# aq6.net
KiCad netlist of a schematic drawn in EAGLE
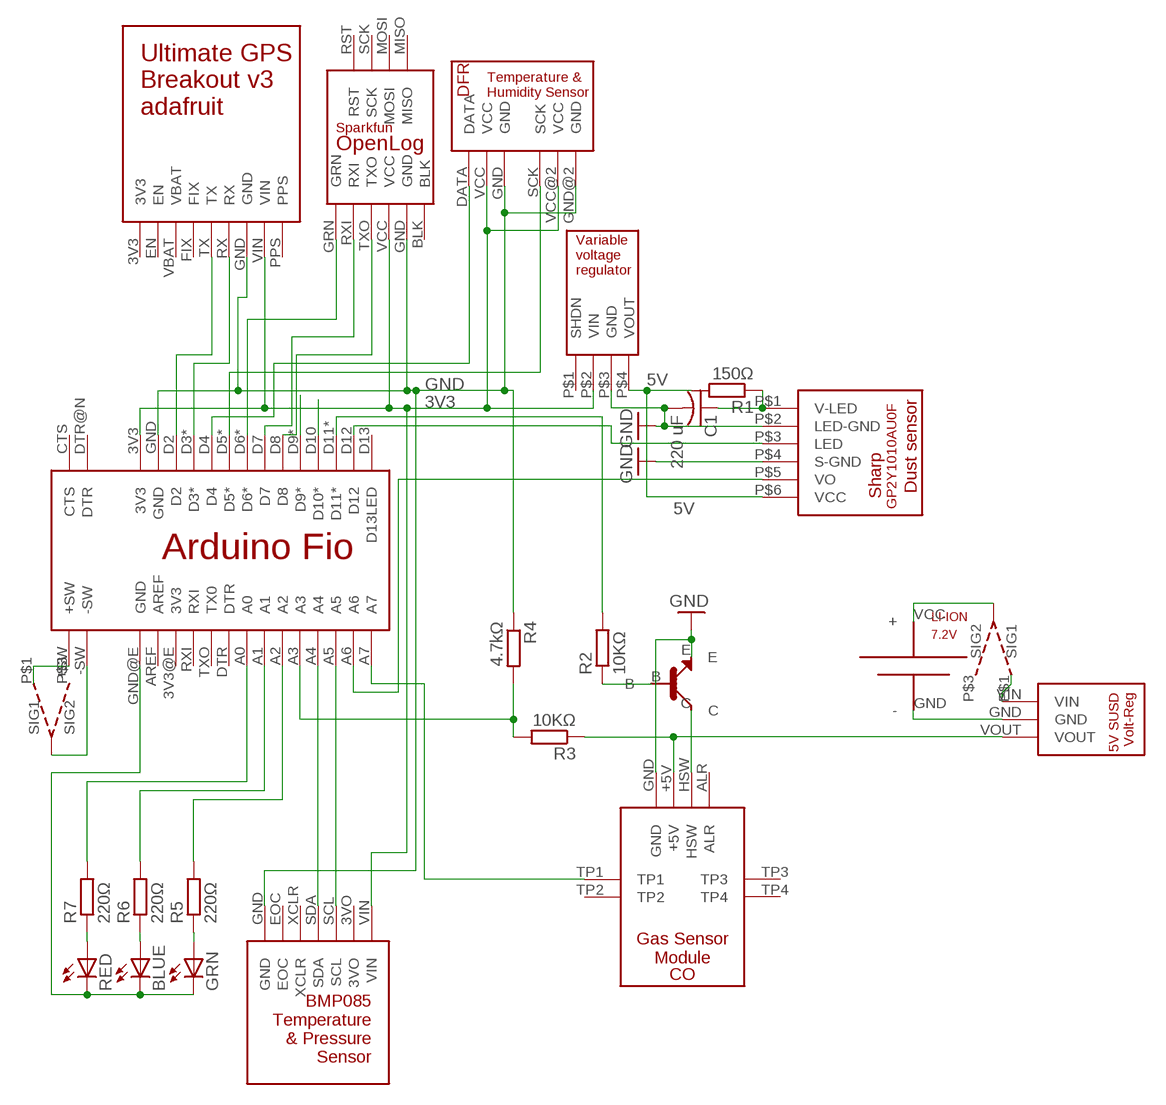
[diagram p0: schematic, sheet 1]

(export (version "E")
  (design (tool "Eeschema 10.0.6"))
  (components
    (comp (ref "BLUE")
      (value "LED5MM")
      (footprint "eagle-import:LED5MM")
      (libsource (lib "eagle-import") (part "LED5MM"))
    )
    (comp (ref "C1")
      (value "220 uF")
      (footprint "eagle-import:C050-025X075")
      (libsource (lib "eagle-import") (part "C-US050-025X075"))
    )
    (comp (ref "CO")
      (value "CO")
      (footprint "eagle-import:GSM_PARALLAX")
      (libsource (lib "eagle-import") (part "CO"))
    )
    (comp (ref "GRN")
      (value "LED5MM")
      (footprint "eagle-import:LED5MM")
      (libsource (lib "eagle-import") (part "LED5MM"))
    )
    (comp (ref "LI-ION")
      (value "7.2V")
      (footprint "eagle-import:BATTERY_WITH_WIRE_HOLES")
      (libsource (lib "eagle-import") (part "BATTERY_WITH_PCB_HOLES"))
    )
    (comp (ref "R1")
      (value "150Ω")
      (footprint "eagle-import:0207_15")
      (libsource (lib "eagle-import") (part "R-EU_0207/15"))
    )
    (comp (ref "R2")
      (value "10KΩ")
      (footprint "eagle-import:0204_7")
      (libsource (lib "eagle-import") (part "resistor_R-EU_0204/7"))
    )
    (comp (ref "R3")
      (value "10KΩ")
      (footprint "eagle-import:0204_7")
      (libsource (lib "eagle-import") (part "resistor_R-EU_0204/7"))
    )
    (comp (ref "R4")
      (value "4.7kΩ")
      (footprint "eagle-import:0204_7")
      (libsource (lib "eagle-import") (part "resistor_R-EU_0204/7"))
    )
    (comp (ref "R5")
      (value "220Ω")
      (footprint "eagle-import:0204_7")
      (libsource (lib "eagle-import") (part "resistor_R-EU_0204/7"))
    )
    (comp (ref "R6")
      (value "220Ω")
      (footprint "eagle-import:0204_7")
      (libsource (lib "eagle-import") (part "resistor_R-EU_0204/7"))
    )
    (comp (ref "R7")
      (value "220Ω")
      (footprint "eagle-import:0204_7")
      (libsource (lib "eagle-import") (part "resistor_R-EU_0204/7"))
    )
    (comp (ref "RED")
      (value "LED5MM")
      (footprint "eagle-import:LED5MM")
      (libsource (lib "eagle-import") (part "LED5MM"))
    )
    (comp (ref "U$1")
      (value "SHARP_DUST_SENSOR6PIN")
      (footprint "eagle-import:6PIN")
      (libsource (lib "eagle-import") (part "SHARP_DUST_SENSOR6PIN"))
    )
    (comp (ref "U$2")
      (value "ARDUINO_FIO")
      (footprint "eagle-import:ARDUINO_FIO")
      (libsource (lib "eagle-import") (part "ARDUINO_FIO"))
    )
    (comp (ref "U$3")
      (value "POLOLU_VAR_VOLTAGE_REG")
      (footprint "eagle-import:POLOLU_VAR_VOLTAGE_REG")
      (libsource (lib "eagle-import") (part "POLOLU_VAR_VOLTAGE_REG"))
    )
    (comp (ref "U$4")
      (value "ADAFRUIT_GPS_V3")
      (footprint "eagle-import:ADAFRUIT_GPS_V3")
      (libsource (lib "eagle-import") (part "ADAFRUIT_GPS_V3"))
    )
    (comp (ref "U$5")
      (value "SPARKFUN_OPENLOG")
      (footprint "eagle-import:SPARKFUN_OPENLOG")
      (libsource (lib "eagle-import") (part "SPARKFUN_OPENLOG"))
    )
    (comp (ref "U$6")
      (value "DFR_TEMP_HUMIDITY")
      (footprint "eagle-import:DFR_TEMP_HUMIDITY")
      (libsource (lib "eagle-import") (part "DFR_TEMP_HUMIDITY"))
    )
    (comp (ref "U$7")
      (value "5V_SUSD_VOLT_REG")
      (footprint "eagle-import:5V_SUSD_VOLT_REG")
      (libsource (lib "eagle-import") (part "5V_SUSD_VOLT_REG"))
    )
    (comp (ref "U$8")
      (value "BMP085")
      (footprint "eagle-import:BMP085")
      (libsource (lib "eagle-import") (part "BMP085"))
    )
    (comp (ref "U$10")
      (value "SWITCH")
      (footprint "eagle-import:SWITCH")
      (libsource (lib "eagle-import") (part "SWITCH"))
    )
    (comp (ref "U$11")
      (value "SWITCH")
      (footprint "eagle-import:SWITCH")
      (libsource (lib "eagle-import") (part "SWITCH"))
    )
    (comp (ref "U$12")
      (value "NPN")
      (footprint "eagle-import:NPN")
      (libsource (lib "eagle-import") (part "NPN"))
    )
  )
  (nets
    (net (code "1") (name "/3V3") (class "Default")
      (node (ref "U$2") (pin "3V3") (pinfunction "3V3_3V3") (pintype "bidirectional"))
      (node (ref "U$3") (pin "P$2") (pinfunction "VIN_P$2") (pintype "bidirectional"))
      (node (ref "U$4") (pin "VIN") (pinfunction "VIN_VIN") (pintype "bidirectional"))
      (node (ref "U$5") (pin "VCC") (pinfunction "VCC_VCC") (pintype "bidirectional"))
      (node (ref "U$6") (pin "VCC") (pinfunction "VCC_VCC") (pintype "bidirectional"))
      (node (ref "U$6") (pin "VCC@2") (pinfunction "VCC_VCC@2") (pintype "bidirectional"))
      (node (ref "U$8") (pin "VIN") (pinfunction "VIN_VIN") (pintype "power_in"))
    )
    (net (code "2") (name "/3VO") (class "Default")
      (node (ref "U$8") (pin "3VO") (pinfunction "3VO_3VO") (pintype "power_in"))
    )
    (net (code "3") (name "/5V") (class "Default")
      (node (ref "R1") (pin "2") (pinfunction "2_2") (pintype "passive"))
      (node (ref "U$1") (pin "P$6") (pinfunction "VCC_P$6") (pintype "bidirectional"))
      (node (ref "U$3") (pin "P$4") (pinfunction "VOUT_P$4") (pintype "bidirectional"))
    )
    (net (code "4") (name "GND") (class "Default")
      (node (ref "BLUE") (pin "K") (pinfunction "C_K") (pintype "passive"))
      (node (ref "C1") (pin "2") (pinfunction "2_2") (pintype "passive"))
      (node (ref "CO") (pin "GND") (pinfunction "GND_GND") (pintype "power_in"))
      (node (ref "GRN") (pin "K") (pinfunction "C_K") (pintype "passive"))
      (node (ref "LI-ION") (pin "GND") (pinfunction "-_GND") (pintype "bidirectional"))
      (node (ref "R4") (pin "1") (pinfunction "1_1") (pintype "passive"))
      (node (ref "RED") (pin "K") (pinfunction "C_K") (pintype "passive"))
      (node (ref "U$1") (pin "P$2") (pinfunction "LED-GND_P$2") (pintype "bidirectional"))
      (node (ref "U$1") (pin "P$4") (pinfunction "S-GND_P$4") (pintype "bidirectional"))
      (node (ref "U$12") (pin "E") (pinfunction "E_E") (pintype "bidirectional"))
      (node (ref "U$2") (pin "GND") (pinfunction "GND_GND") (pintype "bidirectional"))
      (node (ref "U$2") (pin "GND@E") (pinfunction "GND_GND@E") (pintype "bidirectional"))
      (node (ref "U$3") (pin "P$3") (pinfunction "GND_P$3") (pintype "bidirectional"))
      (node (ref "U$4") (pin "GND") (pinfunction "GND_GND") (pintype "bidirectional"))
      (node (ref "U$5") (pin "GND") (pinfunction "GND_GND") (pintype "bidirectional"))
      (node (ref "U$6") (pin "GND") (pinfunction "GND_GND") (pintype "bidirectional"))
      (node (ref "U$6") (pin "GND@2") (pinfunction "GND_GND@2") (pintype "bidirectional"))
      (node (ref "U$7") (pin "GND") (pinfunction "GND_GND") (pintype "bidirectional"))
      (node (ref "U$8") (pin "GND") (pinfunction "GND_GND") (pintype "power_in"))
    )
    (net (code "5") (name "Net-(BLUE-PadA)") (class "Default")
      (node (ref "BLUE") (pin "A") (pinfunction "A_A") (pintype "passive"))
      (node (ref "R6") (pin "1") (pinfunction "1_1") (pintype "passive"))
    )
    (net (code "6") (name "Net-(CO-Pad+5V)") (class "Default")
      (node (ref "CO") (pin "+5V") (pinfunction "+5V_+5V") (pintype "power_in"))
      (node (ref "R3") (pin "1") (pinfunction "1_1") (pintype "passive"))
      (node (ref "U$7") (pin "VOUT") (pinfunction "VOUT_VOUT") (pintype "bidirectional"))
    )
    (net (code "7") (name "Net-(CO-PadHSW)") (class "Default")
      (node (ref "CO") (pin "HSW") (pinfunction "HSW_HSW") (pintype "bidirectional"))
      (node (ref "U$12") (pin "C") (pinfunction "C_C") (pintype "bidirectional"))
    )
    (net (code "8") (name "Net-(CO-PadTP1)") (class "Default")
      (node (ref "CO") (pin "TP1") (pinfunction "TP1_TP1") (pintype "output"))
      (node (ref "U$2") (pin "A7") (pinfunction "A7_A7") (pintype "bidirectional"))
    )
    (net (code "9") (name "Net-(GRN-PadA)") (class "Default")
      (node (ref "GRN") (pin "A") (pinfunction "A_A") (pintype "passive"))
      (node (ref "R5") (pin "1") (pinfunction "1_1") (pintype "passive"))
    )
    (net (code "10") (name "Net-(LI-ION-+)") (class "Default")
      (node (ref "LI-ION") (pin "VCC") (pinfunction "+_VCC") (pintype "bidirectional"))
      (node (ref "U$11") (pin "P$2") (pinfunction "SIG_OUT_P$2") (pintype "bidirectional"))
    )
    (net (code "11") (name "Net-(R2-Pad1)") (class "Default")
      (node (ref "R2") (pin "1") (pinfunction "1_1") (pintype "passive"))
      (node (ref "U$12") (pin "B") (pinfunction "B_B") (pintype "bidirectional"))
    )
    (net (code "12") (name "Net-(R2-Pad2)") (class "Default")
      (node (ref "R2") (pin "2") (pinfunction "2_2") (pintype "passive"))
      (node (ref "U$2") (pin "D11*") (pinfunction "D11*_D11*") (pintype "bidirectional"))
    )
    (net (code "13") (name "Net-(R3-Pad2)") (class "Default")
      (node (ref "R3") (pin "2") (pinfunction "2_2") (pintype "passive"))
      (node (ref "R4") (pin "2") (pinfunction "2_2") (pintype "passive"))
      (node (ref "U$2") (pin "A3") (pinfunction "A3_A3") (pintype "bidirectional"))
    )
    (net (code "14") (name "Net-(R5-Pad2)") (class "Default")
      (node (ref "R5") (pin "2") (pinfunction "2_2") (pintype "passive"))
      (node (ref "U$2") (pin "A2") (pinfunction "A2_A2") (pintype "bidirectional"))
    )
    (net (code "15") (name "Net-(R6-Pad2)") (class "Default")
      (node (ref "R6") (pin "2") (pinfunction "2_2") (pintype "passive"))
      (node (ref "U$2") (pin "A1") (pinfunction "A1_A1") (pintype "bidirectional"))
    )
    (net (code "16") (name "Net-(R7-Pad1)") (class "Default")
      (node (ref "R7") (pin "1") (pinfunction "1_1") (pintype "passive"))
      (node (ref "RED") (pin "A") (pinfunction "A_A") (pintype "passive"))
    )
    (net (code "17") (name "Net-(R7-Pad2)") (class "Default")
      (node (ref "R7") (pin "2") (pinfunction "2_2") (pintype "passive"))
      (node (ref "U$2") (pin "A0") (pinfunction "A0_A0") (pintype "bidirectional"))
    )
    (net (code "18") (name "Net-(U$1-LED)") (class "Default")
      (node (ref "U$1") (pin "P$3") (pinfunction "LED_P$3") (pintype "bidirectional"))
      (node (ref "U$2") (pin "D12") (pinfunction "D12_D12") (pintype "bidirectional"))
    )
    (net (code "19") (name "Net-(U$1-V-LED)") (class "Default")
      (node (ref "C1") (pin "1") (pinfunction "1_1") (pintype "passive"))
      (node (ref "R1") (pin "1") (pinfunction "1_1") (pintype "passive"))
      (node (ref "U$1") (pin "P$1") (pinfunction "V-LED_P$1") (pintype "bidirectional"))
    )
    (net (code "20") (name "Net-(U$1-VO)") (class "Default")
      (node (ref "U$1") (pin "P$5") (pinfunction "VO_P$5") (pintype "bidirectional"))
      (node (ref "U$2") (pin "A6") (pinfunction "A6_A6") (pintype "bidirectional"))
    )
    (net (code "21") (name "Net-(U$2-PadA4)") (class "Default")
      (node (ref "U$2") (pin "A4") (pinfunction "A4_A4") (pintype "bidirectional"))
      (node (ref "U$8") (pin "SDA") (pinfunction "SDA_SDA") (pintype "bidirectional"))
    )
    (net (code "22") (name "Net-(U$2-PadA5)") (class "Default")
      (node (ref "U$2") (pin "A5") (pinfunction "A5_A5") (pintype "bidirectional"))
      (node (ref "U$8") (pin "SCL") (pinfunction "SCL_SCL") (pintype "bidirectional"))
    )
    (net (code "23") (name "Net-(U$2-PadD2)") (class "Default")
      (node (ref "U$2") (pin "D2") (pinfunction "D2_D2") (pintype "bidirectional"))
      (node (ref "U$4") (pin "TX") (pinfunction "TX_TX") (pintype "bidirectional"))
    )
    (net (code "24") (name "Net-(U$2-PadD3*)") (class "Default")
      (node (ref "U$2") (pin "D3*") (pinfunction "D3*_D3*") (pintype "bidirectional"))
      (node (ref "U$4") (pin "RX") (pinfunction "RX_RX") (pintype "bidirectional"))
    )
    (net (code "25") (name "Net-(U$2-PadD4)") (class "Default")
      (node (ref "U$2") (pin "D4") (pinfunction "D4_D4") (pintype "bidirectional"))
      (node (ref "U$6") (pin "DATA") (pinfunction "DATA_DATA") (pintype "bidirectional"))
    )
    (net (code "26") (name "Net-(U$2-PadD5*)") (class "Default")
      (node (ref "U$2") (pin "D5*") (pinfunction "D5*_D5*") (pintype "bidirectional"))
      (node (ref "U$6") (pin "SCK") (pinfunction "SCK_SCK") (pintype "bidirectional"))
    )
    (net (code "27") (name "Net-(U$2-PadD6*)") (class "Default")
      (node (ref "U$2") (pin "D6*") (pinfunction "D6*_D6*") (pintype "bidirectional"))
      (node (ref "U$5") (pin "GRN") (pinfunction "GRN_GRN") (pintype "bidirectional"))
    )
    (net (code "28") (name "Net-(U$2-PadD7)") (class "Default")
      (node (ref "U$2") (pin "D7") (pinfunction "D7_D7") (pintype "bidirectional"))
      (node (ref "U$5") (pin "RXI") (pinfunction "RXI_RXI") (pintype "bidirectional"))
    )
    (net (code "29") (name "Net-(U$2-PadD8)") (class "Default")
      (node (ref "U$2") (pin "D8") (pinfunction "D8_D8") (pintype "bidirectional"))
      (node (ref "U$5") (pin "TXO") (pinfunction "TXO_TXO") (pintype "bidirectional"))
    )
    (net (code "30") (name "Net-(U$10-SIG1)") (class "Default")
      (node (ref "U$10") (pin "P$1") (pinfunction "SIG1_P$1") (pintype "bidirectional"))
      (node (ref "U$2") (pin "+SW") (pinfunction "+SW_+SW") (pintype "bidirectional"))
    )
    (net (code "31") (name "Net-(U$10-SIG_OUT)") (class "Default")
      (node (ref "U$10") (pin "P$2") (pinfunction "SIG_OUT_P$2") (pintype "bidirectional"))
      (node (ref "U$2") (pin "-SW") (pinfunction "-SW_-SW") (pintype "bidirectional"))
    )
    (net (code "32") (name "Net-(U$11-SIG1)") (class "Default")
      (node (ref "U$11") (pin "P$1") (pinfunction "SIG1_P$1") (pintype "bidirectional"))
      (node (ref "U$7") (pin "VIN") (pinfunction "VIN_VIN") (pintype "bidirectional"))
    )
    (net (code "33") (name "unconnected-(CO-PadALR)") (class "Default")
      (node (ref "CO") (pin "ALR") (pinfunction "ALR_ALR") (pintype "bidirectional"))
    )
    (net (code "34") (name "unconnected-(CO-PadTP2)") (class "Default")
      (node (ref "CO") (pin "TP2") (pinfunction "TP2_TP2") (pintype "output"))
    )
    (net (code "35") (name "unconnected-(CO-PadTP3)") (class "Default")
      (node (ref "CO") (pin "TP3") (pinfunction "TP3_TP3") (pintype "output"))
    )
    (net (code "36") (name "unconnected-(CO-PadTP4)") (class "Default")
      (node (ref "CO") (pin "TP4") (pinfunction "TP4_TP4") (pintype "output"))
    )
    (net (code "37") (name "unconnected-(U$2-3V3-Pad3V3@E)") (class "Default")
      (node (ref "U$2") (pin "3V3@E") (pinfunction "3V3_3V3@E") (pintype "bidirectional"))
    )
    (net (code "38") (name "unconnected-(U$2-D10*-PadD10)") (class "Default")
      (node (ref "U$2") (pin "D10") (pinfunction "D10*_D10") (pintype "bidirectional"))
    )
    (net (code "39") (name "unconnected-(U$2-D13LED-PadD13)") (class "Default")
      (node (ref "U$2") (pin "D13") (pinfunction "D13LED_D13") (pintype "bidirectional"))
    )
    (net (code "40") (name "unconnected-(U$2-DTR-PadDTR@N)") (class "Default")
      (node (ref "U$2") (pin "DTR@N") (pinfunction "DTR_DTR@N") (pintype "bidirectional"))
    )
    (net (code "41") (name "unconnected-(U$2-PadAREF)") (class "Default")
      (node (ref "U$2") (pin "AREF") (pinfunction "AREF_AREF") (pintype "bidirectional"))
    )
    (net (code "42") (name "unconnected-(U$2-PadCTS)") (class "Default")
      (node (ref "U$2") (pin "CTS") (pinfunction "CTS_CTS") (pintype "bidirectional"))
    )
    (net (code "43") (name "unconnected-(U$2-PadD9*)") (class "Default")
      (node (ref "U$2") (pin "D9*") (pinfunction "D9*_D9*") (pintype "bidirectional"))
    )
    (net (code "44") (name "unconnected-(U$2-PadDTR)") (class "Default")
      (node (ref "U$2") (pin "DTR") (pinfunction "DTR_DTR") (pintype "bidirectional"))
    )
    (net (code "45") (name "unconnected-(U$2-PadRXI)") (class "Default")
      (node (ref "U$2") (pin "RXI") (pinfunction "RXI_RXI") (pintype "bidirectional"))
    )
    (net (code "46") (name "unconnected-(U$2-TX0-PadTXO)") (class "Default")
      (node (ref "U$2") (pin "TXO") (pinfunction "TX0_TXO") (pintype "bidirectional"))
    )
    (net (code "47") (name "unconnected-(U$3-SHDN-PadP$1)") (class "Default")
      (node (ref "U$3") (pin "P$1") (pinfunction "SHDN_P$1") (pintype "bidirectional"))
    )
    (net (code "48") (name "unconnected-(U$4-Pad3V3)") (class "Default")
      (node (ref "U$4") (pin "3V3") (pinfunction "3V3_3V3") (pintype "bidirectional"))
    )
    (net (code "49") (name "unconnected-(U$4-PadEN)") (class "Default")
      (node (ref "U$4") (pin "EN") (pinfunction "EN_EN") (pintype "bidirectional"))
    )
    (net (code "50") (name "unconnected-(U$4-PadFIX)") (class "Default")
      (node (ref "U$4") (pin "FIX") (pinfunction "FIX_FIX") (pintype "bidirectional"))
    )
    (net (code "51") (name "unconnected-(U$4-PadPPS)") (class "Default")
      (node (ref "U$4") (pin "PPS") (pinfunction "PPS_PPS") (pintype "bidirectional"))
    )
    (net (code "52") (name "unconnected-(U$4-PadVBAT)") (class "Default")
      (node (ref "U$4") (pin "VBAT") (pinfunction "VBAT_VBAT") (pintype "bidirectional"))
    )
    (net (code "53") (name "unconnected-(U$5-PadBLK)") (class "Default")
      (node (ref "U$5") (pin "BLK") (pinfunction "BLK_BLK") (pintype "bidirectional"))
    )
    (net (code "54") (name "unconnected-(U$5-PadMISO)") (class "Default")
      (node (ref "U$5") (pin "MISO") (pinfunction "MISO_MISO") (pintype "bidirectional"))
    )
    (net (code "55") (name "unconnected-(U$5-PadMOSI)") (class "Default")
      (node (ref "U$5") (pin "MOSI") (pinfunction "MOSI_MOSI") (pintype "bidirectional"))
    )
    (net (code "56") (name "unconnected-(U$5-PadRST)") (class "Default")
      (node (ref "U$5") (pin "RST") (pinfunction "RST_RST") (pintype "bidirectional"))
    )
    (net (code "57") (name "unconnected-(U$5-PadSCK)") (class "Default")
      (node (ref "U$5") (pin "SCK") (pinfunction "SCK_SCK") (pintype "bidirectional"))
    )
    (net (code "58") (name "unconnected-(U$8-PadEOC)") (class "Default")
      (node (ref "U$8") (pin "EOC") (pinfunction "EOC_EOC") (pintype "bidirectional"))
    )
    (net (code "59") (name "unconnected-(U$8-PadXCLR)") (class "Default")
      (node (ref "U$8") (pin "XCLR") (pinfunction "XCLR_XCLR") (pintype "bidirectional"))
    )
    (net (code "60") (name "unconnected-(U$10-SIG2-PadP$3)") (class "Default")
      (node (ref "U$10") (pin "P$3") (pinfunction "SIG2_P$3") (pintype "bidirectional"))
    )
    (net (code "61") (name "unconnected-(U$11-SIG2-PadP$3)") (class "Default")
      (node (ref "U$11") (pin "P$3") (pinfunction "SIG2_P$3") (pintype "bidirectional"))
    )
  )
)
